# UBX_NORA_B1_SCHEM_0002_Power.net
KiCad netlist of a schematic drawn in Altium Designer
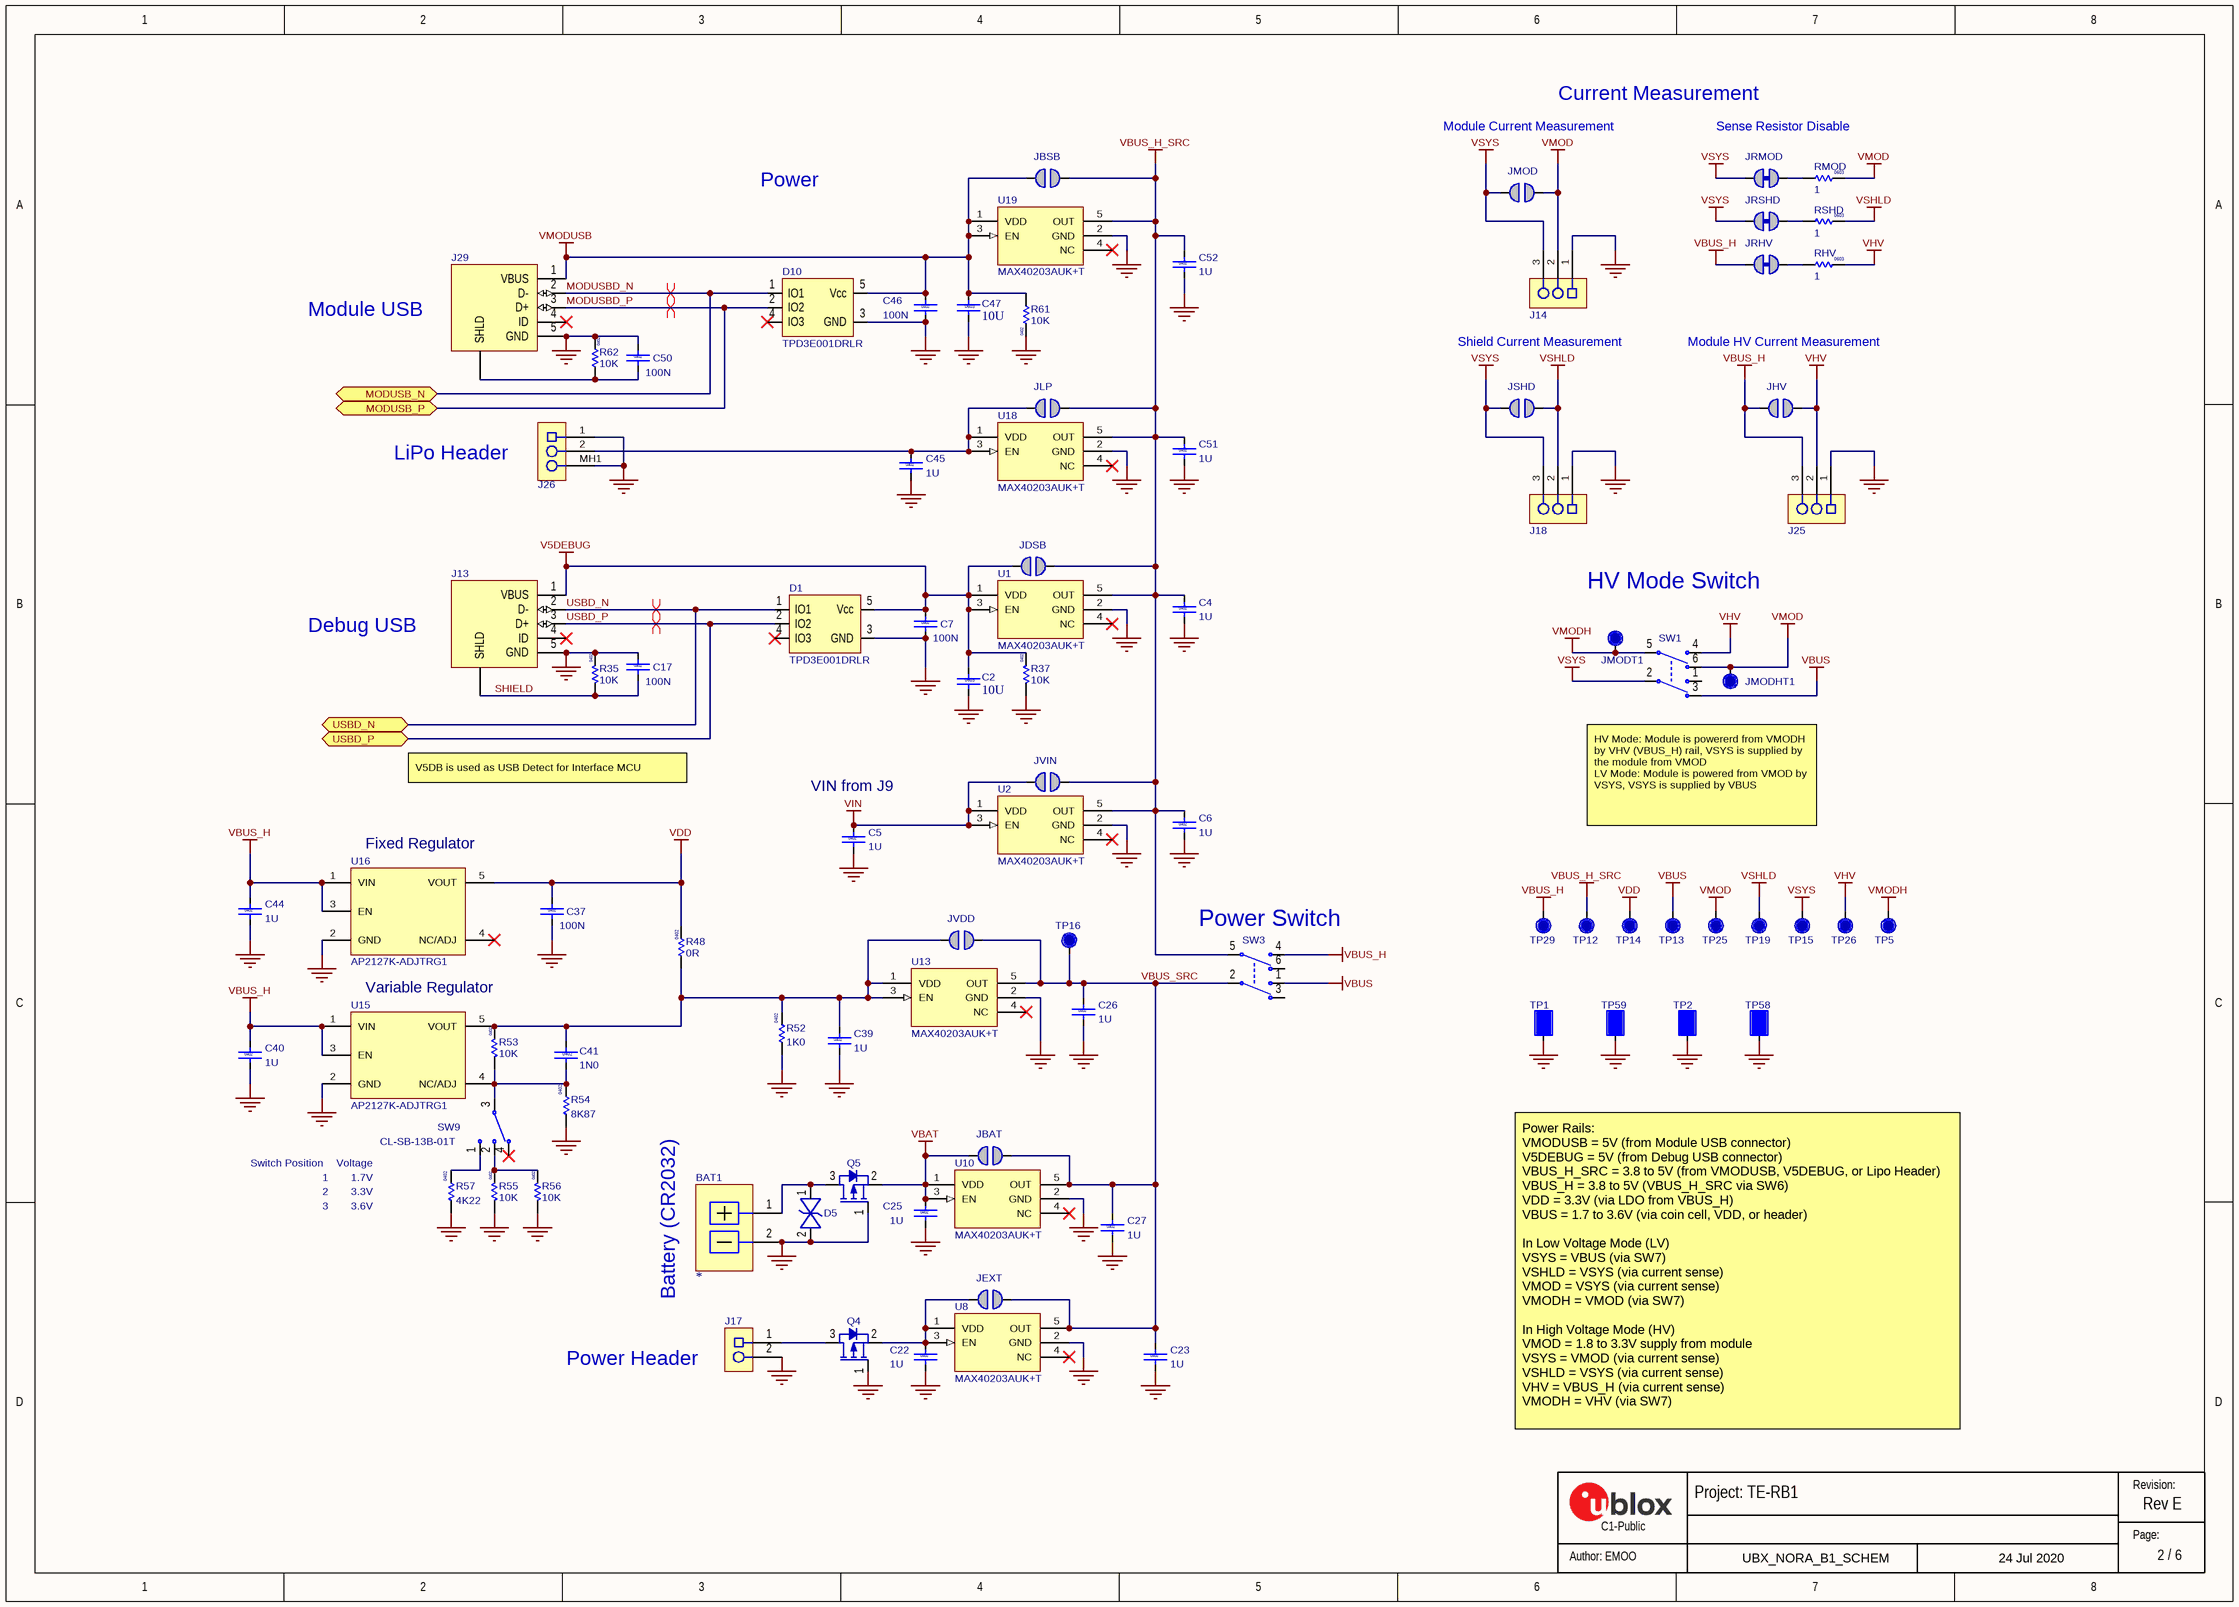
[diagram p0: UBX_NORA_B1_SCHEM_0002_Power.SchDoc]

(export (version "E")
  (design (tool "Eeschema 10.0.6"))
  (components
    (comp (ref "BAT1")
      (value "UBXH03-0000010")
      (footprint "Battery_S8211-46R_large")
      (description "BATTERY HOLDER COIN SMT CR2016 CR2020 CR2025 CR2032 HARWIN S8211-46R")
      (fields (field (name "MANUFACTURER P/N") "*") (field (name "EDITOR") "eric.moog"))
      (libsource (lib "UBX_Parts_DB_Lib") (part "Battery_2Pin"))
    )
    (comp (ref "C2")
      (value "10U")
      (footprint "CAP 0603 HD")
      (description "CAP CER X5R 0603 10U 20% 10V")
      (fields
        (field (name "SIZE") "0603")
        (field (name "PART NUMBER") "UBXH01-0000040")
        (field (name "TOLERANCE") "20%")
        (field (name "EDITOR") "pierpaolo.arban")
        (field (name "RELEASED BY") "matej.budin")
      )
      (libsource (lib "UBX_Parts_DB_Lib") (part "Cap Chip"))
    )
    (comp (ref "C4")
      (value "1U")
      (footprint "Cap 0402 HD")
      (description "CAP CER X5R 0402 1U 10% 10V")
      (fields
        (field (name "SIZE") "0402")
        (field (name "PART NUMBER") "UBXH01-0000248")
        (field (name "TOLERANCE") "10%")
        (field (name "EDITOR") "michael.hein")
        (field (name "RELEASED BY") "igor.shevchenko")
      )
      (libsource (lib "UBX_Parts_DB_Lib") (part "Cap Chip"))
    )
    (comp (ref "C5")
      (value "1U")
      (footprint "Cap 0402 HD")
      (description "CAP CER X5R 0402 1U 10% 10V")
      (fields
        (field (name "SIZE") "0402")
        (field (name "PART NUMBER") "UBXH01-0000248")
        (field (name "TOLERANCE") "10%")
        (field (name "EDITOR") "michael.hein")
        (field (name "RELEASED BY") "igor.shevchenko")
      )
      (libsource (lib "UBX_Parts_DB_Lib") (part "Cap Chip"))
    )
    (comp (ref "C6")
      (value "1U")
      (footprint "Cap 0402 HD")
      (description "CAP CER X5R 0402 1U 10% 10V")
      (fields
        (field (name "SIZE") "0402")
        (field (name "PART NUMBER") "UBXH01-0000248")
        (field (name "TOLERANCE") "10%")
        (field (name "EDITOR") "michael.hein")
        (field (name "RELEASED BY") "igor.shevchenko")
      )
      (libsource (lib "UBX_Parts_DB_Lib") (part "Cap Chip"))
    )
    (comp (ref "C7")
      (value "100N")
      (footprint "Cap 0402 HD")
      (description "CAP CER X5R 0402 100N 10% 10V")
      (fields
        (field (name "SIZE") "0402")
        (field (name "PART NUMBER") "UBXH01-2021002")
        (field (name "TOLERANCE") "10%")
        (field (name "EDITOR") "roland.rust")
        (field (name "RELEASED BY") "roland.rust")
      )
      (libsource (lib "UBX_Parts_DB_Lib") (part "Cap Chip"))
    )
    (comp (ref "C17")
      (value "100N")
      (footprint "Cap 0402 HD")
      (description "CAP CER X5R 0402 100N 10% 10V")
      (fields
        (field (name "SIZE") "0402")
        (field (name "PART NUMBER") "UBXH01-2021002")
        (field (name "TOLERANCE") "10%")
        (field (name "EDITOR") "roland.rust")
        (field (name "RELEASED BY") "roland.rust")
      )
      (libsource (lib "UBX_Parts_DB_Lib") (part "Cap Chip"))
    )
    (comp (ref "C22")
      (value "1U")
      (footprint "Cap 0402 HD")
      (description "CAP CER X5R 0402 1U 10% 10V")
      (fields
        (field (name "SIZE") "0402")
        (field (name "PART NUMBER") "UBXH01-0000248")
        (field (name "TOLERANCE") "10%")
        (field (name "EDITOR") "michael.hein")
        (field (name "RELEASED BY") "igor.shevchenko")
      )
      (libsource (lib "UBX_Parts_DB_Lib") (part "Cap Chip"))
    )
    (comp (ref "C23")
      (value "1U")
      (footprint "Cap 0402 HD")
      (description "CAP CER X5R 0402 1U 10% 10V")
      (fields
        (field (name "SIZE") "0402")
        (field (name "PART NUMBER") "UBXH01-0000248")
        (field (name "TOLERANCE") "10%")
        (field (name "EDITOR") "michael.hein")
        (field (name "RELEASED BY") "igor.shevchenko")
      )
      (libsource (lib "UBX_Parts_DB_Lib") (part "Cap Chip"))
    )
    (comp (ref "C25")
      (value "1U")
      (footprint "Cap 0402 HD")
      (description "CAP CER X5R 0402 1U 10% 10V")
      (fields
        (field (name "SIZE") "0402")
        (field (name "PART NUMBER") "UBXH01-0000248")
        (field (name "TOLERANCE") "10%")
        (field (name "EDITOR") "michael.hein")
        (field (name "RELEASED BY") "igor.shevchenko")
      )
      (libsource (lib "UBX_Parts_DB_Lib") (part "Cap Chip"))
    )
    (comp (ref "C26")
      (value "1U")
      (footprint "Cap 0402 HD")
      (description "CAP CER X5R 0402 1U 10% 10V")
      (fields
        (field (name "SIZE") "0402")
        (field (name "PART NUMBER") "UBXH01-0000248")
        (field (name "TOLERANCE") "10%")
        (field (name "EDITOR") "michael.hein")
        (field (name "RELEASED BY") "igor.shevchenko")
      )
      (libsource (lib "UBX_Parts_DB_Lib") (part "Cap Chip"))
    )
    (comp (ref "C27")
      (value "1U")
      (footprint "Cap 0402 HD")
      (description "CAP CER X5R 0402 1U 10% 10V")
      (fields
        (field (name "SIZE") "0402")
        (field (name "PART NUMBER") "UBXH01-0000248")
        (field (name "TOLERANCE") "10%")
        (field (name "EDITOR") "michael.hein")
        (field (name "RELEASED BY") "igor.shevchenko")
      )
      (libsource (lib "UBX_Parts_DB_Lib") (part "Cap Chip"))
    )
    (comp (ref "C37")
      (value "100N")
      (footprint "Cap 0402 HD")
      (description "CAP CER X5R 0402 100N 10% 10V")
      (fields
        (field (name "SIZE") "0402")
        (field (name "PART NUMBER") "UBXH01-2021002")
        (field (name "TOLERANCE") "10%")
        (field (name "EDITOR") "roland.rust")
        (field (name "RELEASED BY") "roland.rust")
      )
      (libsource (lib "UBX_Parts_DB_Lib") (part "Cap Chip"))
    )
    (comp (ref "C39")
      (value "1U")
      (footprint "Cap 0402 HD")
      (description "CAP CER X5R 0402 1U 10% 10V")
      (fields
        (field (name "SIZE") "0402")
        (field (name "PART NUMBER") "UBXH01-0000248")
        (field (name "TOLERANCE") "10%")
        (field (name "EDITOR") "michael.hein")
        (field (name "RELEASED BY") "igor.shevchenko")
      )
      (libsource (lib "UBX_Parts_DB_Lib") (part "Cap Chip"))
    )
    (comp (ref "C40")
      (value "1U")
      (footprint "Cap 0402 HD")
      (description "CAP CER X5R 0402 1U 10% 10V")
      (fields
        (field (name "SIZE") "0402")
        (field (name "PART NUMBER") "UBXH01-0000248")
        (field (name "TOLERANCE") "10%")
        (field (name "EDITOR") "michael.hein")
        (field (name "RELEASED BY") "igor.shevchenko")
      )
      (libsource (lib "UBX_Parts_DB_Lib") (part "Cap Chip"))
    )
    (comp (ref "C41")
      (value "1N0")
      (footprint "Cap 0402 HD")
      (description "CAP CER X7R 0402 1N0 10% 50V")
      (fields
        (field (name "SIZE") "0402")
        (field (name "PART NUMBER") "UBXH01-0000013")
        (field (name "TOLERANCE") "10%")
        (field (name "EDITOR") "massimo.vlacci")
        (field (name "RELEASED BY") "dario.antonaz")
      )
      (libsource (lib "UBX_Parts_DB_Lib") (part "Cap Chip"))
    )
    (comp (ref "C44")
      (value "1U")
      (footprint "Cap 0402 HD")
      (description "CAP CER X5R 0402 1U 10% 10V")
      (fields
        (field (name "SIZE") "0402")
        (field (name "PART NUMBER") "UBXH01-0000248")
        (field (name "TOLERANCE") "10%")
        (field (name "EDITOR") "michael.hein")
        (field (name "RELEASED BY") "igor.shevchenko")
      )
      (libsource (lib "UBX_Parts_DB_Lib") (part "Cap Chip"))
    )
    (comp (ref "C45")
      (value "1U")
      (footprint "Cap 0402 HD")
      (description "CAP CER X5R 0402 1U 10% 10V")
      (fields
        (field (name "SIZE") "0402")
        (field (name "PART NUMBER") "UBXH01-0000248")
        (field (name "TOLERANCE") "10%")
        (field (name "EDITOR") "michael.hein")
        (field (name "RELEASED BY") "igor.shevchenko")
      )
      (libsource (lib "UBX_Parts_DB_Lib") (part "Cap Chip"))
    )
    (comp (ref "C46")
      (value "100N")
      (footprint "Cap 0402 HD")
      (description "CAP CER X5R 0402 100N 10% 10V")
      (fields
        (field (name "SIZE") "0402")
        (field (name "PART NUMBER") "UBXH01-2021002")
        (field (name "TOLERANCE") "10%")
        (field (name "EDITOR") "roland.rust")
        (field (name "RELEASED BY") "roland.rust")
      )
      (libsource (lib "UBX_Parts_DB_Lib") (part "Cap Chip"))
    )
    (comp (ref "C47")
      (value "10U")
      (footprint "CAP 0603 HD")
      (description "CAP CER X5R 0603 10U 20% 10V")
      (fields
        (field (name "SIZE") "0603")
        (field (name "PART NUMBER") "UBXH01-0000040")
        (field (name "TOLERANCE") "20%")
        (field (name "EDITOR") "pierpaolo.arban")
        (field (name "RELEASED BY") "matej.budin")
      )
      (libsource (lib "UBX_Parts_DB_Lib") (part "Cap Chip"))
    )
    (comp (ref "C50")
      (value "100N")
      (footprint "Cap 0402 HD")
      (description "CAP CER X5R 0402 100N 10% 10V")
      (fields
        (field (name "SIZE") "0402")
        (field (name "PART NUMBER") "UBXH01-2021002")
        (field (name "TOLERANCE") "10%")
        (field (name "EDITOR") "roland.rust")
        (field (name "RELEASED BY") "roland.rust")
      )
      (libsource (lib "UBX_Parts_DB_Lib") (part "Cap Chip"))
    )
    (comp (ref "C51")
      (value "1U")
      (footprint "Cap 0402 HD")
      (description "CAP CER X5R 0402 1U 10% 10V")
      (fields
        (field (name "SIZE") "0402")
        (field (name "PART NUMBER") "UBXH01-0000248")
        (field (name "TOLERANCE") "10%")
        (field (name "EDITOR") "michael.hein")
        (field (name "RELEASED BY") "igor.shevchenko")
      )
      (libsource (lib "UBX_Parts_DB_Lib") (part "Cap Chip"))
    )
    (comp (ref "C52")
      (value "1U")
      (footprint "Cap 0402 HD")
      (description "CAP CER X5R 0402 1U 10% 10V")
      (fields
        (field (name "SIZE") "0402")
        (field (name "PART NUMBER") "UBXH01-0000248")
        (field (name "TOLERANCE") "10%")
        (field (name "EDITOR") "michael.hein")
        (field (name "RELEASED BY") "igor.shevchenko")
      )
      (libsource (lib "UBX_Parts_DB_Lib") (part "Cap Chip"))
    )
    (comp (ref "D1")
      (value "UBXH07-0000086")
      (footprint "SOT-553")
      (description "TVS DIODE 5.5VWM")
      (fields
        (field (name "MANUFACTURER P/N") "TPD3E001DRLR")
        (field (name "MANUFACTURER") "Texas Instruments")
        (field (name "EDITOR") "hozaifa.abdelgadir")
      )
      (libsource (lib "UBX_Parts_DB_Lib") (part "TPD3E001"))
    )
    (comp (ref "D5")
      (value "UBXH07-0000034")
      (footprint "SOD-923")
      (description "ESD PROTECTION DIODE ULTRA LOW LEAKAGE SOD923 ON SEMI 3V3")
      (fields
        (field (name "MANUFACTURER") "ON Semiconductor")
        (field (name "EDITOR") "pierpaolo.arban")
        (field (name "RELEASED BY") "dario.antonaz")
      )
      (libsource (lib "UBX_Parts_DB_Lib") (part "Diode_TVS"))
    )
    (comp (ref "D10")
      (value "UBXH07-0000086")
      (footprint "SOT-553")
      (description "TVS DIODE 5.5VWM")
      (fields
        (field (name "MANUFACTURER P/N") "TPD3E001DRLR")
        (field (name "MANUFACTURER") "Texas Instruments")
        (field (name "EDITOR") "hozaifa.abdelgadir")
      )
      (libsource (lib "UBX_Parts_DB_Lib") (part "TPD3E001"))
    )
    (comp (ref "J13")
      (value "UBXH04-0000804")
      (footprint "USB_MICRO_RA_W-2TABS")
      (description "CONN RECEPTACLE USB MICRO B 5-PIN SMD TH RA 5.5V 1.8A")
      (fields
        (field (name "MANUFACTURER") "Amphenol Commercial Products (Amphenol ICC)")
        (field (name "EDITOR") "eric.moog")
      )
      (libsource (lib "UBX_Parts_DB_Lib") (part "USB_W-Shield"))
    )
    (comp (ref "J14")
      (value "UBXH04-0000792")
      (footprint "HDR-0.1P-3Pin-1Row-SMT")
      (description "1-ROW SMD CONN 100MIL GRID 3 -PIN 100V 3A")
      (fields (field (name "MANUFACTURER") "HARWiN") (field (name "EDITOR") "eric.moog"))
      (libsource (lib "UBX_Parts_DB_Lib") (part "CON-3Pin_1Row"))
    )
    (comp (ref "J17")
      (value "UBXH04-0000026")
      (footprint "HDR-0.1P-2PIN-TH")
      (description "1-ROW TH-PCB SOCKETS 100MIL GRID 2-PIN 0.64MM SQUARE POLARIZE")
      (fields
        (field (name "MANUFACTURER") "HARWiN")
        (field (name "EDITOR") "roland.rust")
        (field (name "RELEASED BY") "alvaro.nussbaum")
      )
      (libsource (lib "UBX_Parts_DB_Lib") (part "CON-2Pin_1Row"))
    )
    (comp (ref "J18")
      (value "UBXH04-0000792")
      (footprint "HDR-0.1P-3Pin-1Row-SMT")
      (description "1-ROW SMD CONN 100MIL GRID 3 -PIN 100V 3A")
      (fields (field (name "MANUFACTURER") "HARWiN") (field (name "EDITOR") "eric.moog"))
      (libsource (lib "UBX_Parts_DB_Lib") (part "CON-3Pin_1Row"))
    )
    (comp (ref "J25")
      (value "UBXH04-0000792")
      (footprint "HDR-0.1P-3Pin-1Row-SMT")
      (description "1-ROW SMD CONN 100MIL GRID 3 -PIN 100V 3A")
      (fields (field (name "MANUFACTURER") "HARWiN") (field (name "EDITOR") "eric.moog"))
      (libsource (lib "UBX_Parts_DB_Lib") (part "CON-3Pin_1Row"))
    )
    (comp (ref "J26")
      (value "UBXH04-0000791")
      (footprint "B2B-PH-SM4-TB")
      (description "CONN 1-ROW SMT 2.0MM GRID 2-PIN VERT 100V 2A")
      (fields
        (field (name "VOLTAGE") "None")
        (field (name "MANUFACTURER") "JST")
        (field (name "EDITOR") "eric.moog")
      )
      (libsource (lib "UBX_Parts_DB_Lib") (part "CON-2Pin_1Row_W-MH"))
    )
    (comp (ref "J29")
      (value "UBXH04-0000804")
      (footprint "USB_MICRO_RA_W-2TABS")
      (description "CONN RECEPTACLE USB MICRO B 5-PIN SMD TH RA 5.5V 1.8A")
      (fields
        (field (name "MANUFACTURER") "Amphenol Commercial Products (Amphenol ICC)")
        (field (name "EDITOR") "eric.moog")
      )
      (libsource (lib "UBX_Parts_DB_Lib") (part "USB_W-Shield"))
    )
    (comp (ref "JBAT")
      (value "UBXH00-0000082")
      (footprint "Solderbridge-Open")
      (description "SOLDERBRIDGE-OPEN")
      (fields (field (name "EDITOR") "aneeb.sohail"))
      (libsource (lib "UBX_Parts_DB_Lib") (part "Solderbridge-Open"))
    )
    (comp (ref "JBSB")
      (value "UBXH00-0000082")
      (footprint "Solderbridge-Open")
      (description "SOLDERBRIDGE-OPEN")
      (fields (field (name "EDITOR") "aneeb.sohail"))
      (libsource (lib "UBX_Parts_DB_Lib") (part "Solderbridge-Open"))
    )
    (comp (ref "JDSB")
      (value "UBXH00-0000082")
      (footprint "Solderbridge-Open")
      (description "SOLDERBRIDGE-OPEN")
      (fields (field (name "EDITOR") "aneeb.sohail"))
      (libsource (lib "UBX_Parts_DB_Lib") (part "Solderbridge-Open"))
    )
    (comp (ref "JEXT")
      (value "UBXH00-0000082")
      (footprint "Solderbridge-Open")
      (description "SOLDERBRIDGE-OPEN")
      (fields (field (name "EDITOR") "aneeb.sohail"))
      (libsource (lib "UBX_Parts_DB_Lib") (part "Solderbridge-Open"))
    )
    (comp (ref "JHV")
      (value "UBXH00-0000082")
      (footprint "Solderbridge-Open")
      (description "SOLDERBRIDGE-OPEN")
      (fields (field (name "EDITOR") "aneeb.sohail"))
      (libsource (lib "UBX_Parts_DB_Lib") (part "Solderbridge-Open"))
    )
    (comp (ref "JLP")
      (value "UBXH00-0000082")
      (footprint "Solderbridge-Open")
      (description "SOLDERBRIDGE-OPEN")
      (fields (field (name "EDITOR") "aneeb.sohail"))
      (libsource (lib "UBX_Parts_DB_Lib") (part "Solderbridge-Open"))
    )
    (comp (ref "JMOD")
      (value "UBXH00-0000082")
      (footprint "Solderbridge-Open")
      (description "SOLDERBRIDGE-OPEN")
      (fields (field (name "EDITOR") "aneeb.sohail"))
      (libsource (lib "UBX_Parts_DB_Lib") (part "Solderbridge-Open"))
    )
    (comp (ref "JMODHT1")
      (value "TP")
      (footprint "TP10R")
      (description "TESTPOINT 1MM CIRCULAR")
      (fields (field (name "PART NUMBER") "UBXH00-0000096") (field (name "EDITOR") "eric.moog"))
      (libsource (lib "UBX_Parts_DB_Lib") (part "TP_R"))
    )
    (comp (ref "JMODT1")
      (value "TP")
      (footprint "TP10R")
      (description "TESTPOINT 1MM CIRCULAR")
      (fields (field (name "PART NUMBER") "UBXH00-0000096") (field (name "EDITOR") "eric.moog"))
      (libsource (lib "UBX_Parts_DB_Lib") (part "TP_R"))
    )
    (comp (ref "JRHV")
      (value "UBXH00-0000084")
      (footprint "Solderbridge-Short")
      (description "SOLDERBRIDGE-SHORT")
      (fields (field (name "EDITOR") "aneeb.sohail"))
      (libsource (lib "UBX_Parts_DB_Lib") (part "Solderbridge-Short"))
    )
    (comp (ref "JRMOD")
      (value "UBXH00-0000084")
      (footprint "Solderbridge-Short")
      (description "SOLDERBRIDGE-SHORT")
      (fields (field (name "EDITOR") "aneeb.sohail"))
      (libsource (lib "UBX_Parts_DB_Lib") (part "Solderbridge-Short"))
    )
    (comp (ref "JRSHD")
      (value "UBXH00-0000084")
      (footprint "Solderbridge-Short")
      (description "SOLDERBRIDGE-SHORT")
      (fields (field (name "EDITOR") "aneeb.sohail"))
      (libsource (lib "UBX_Parts_DB_Lib") (part "Solderbridge-Short"))
    )
    (comp (ref "JSHD")
      (value "UBXH00-0000082")
      (footprint "Solderbridge-Open")
      (description "SOLDERBRIDGE-OPEN")
      (fields (field (name "EDITOR") "aneeb.sohail"))
      (libsource (lib "UBX_Parts_DB_Lib") (part "Solderbridge-Open"))
    )
    (comp (ref "JVDD")
      (value "UBXH00-0000082")
      (footprint "Solderbridge-Open")
      (description "SOLDERBRIDGE-OPEN")
      (fields (field (name "EDITOR") "aneeb.sohail"))
      (libsource (lib "UBX_Parts_DB_Lib") (part "Solderbridge-Open"))
    )
    (comp (ref "JVIN")
      (value "UBXH00-0000082")
      (footprint "Solderbridge-Open")
      (description "SOLDERBRIDGE-OPEN")
      (fields (field (name "EDITOR") "aneeb.sohail"))
      (libsource (lib "UBX_Parts_DB_Lib") (part "Solderbridge-Open"))
    )
    (comp (ref "Q4")
      (value "UBXH20-0000087")
      (footprint "SOT-523")
      (description "P-CHANNEL MOSFET DIODES SOT-523 DMG1013T-7 20V 460mA")
      (fields (field (name "EDITOR") "eric.moog"))
      (libsource (lib "UBX_Parts_DB_Lib") (part "MOSFET-P"))
    )
    (comp (ref "Q5")
      (value "UBXH20-0000087")
      (footprint "SOT-523")
      (description "P-CHANNEL MOSFET DIODES SOT-523 DMG1013T-7 20V 460mA")
      (fields (field (name "EDITOR") "eric.moog"))
      (libsource (lib "UBX_Parts_DB_Lib") (part "MOSFET-P"))
    )
    (comp (ref "R35")
      (value "10K")
      (footprint "RES 0402 HD")
      (description "RES THICK FILM CHIP 0402 10K 1% 63mW")
      (fields
        (field (name "SIZE") "0402")
        (field (name "PART NUMBER") "UBXH18-0000065")
        (field (name "TOLERANCE") "1%")
        (field (name "EDITOR") "erian.bezhani")
        (field (name "RELEASED BY") "massimo.vlacci")
      )
      (libsource (lib "UBX_Parts_DB_Lib") (part "Res sm"))
    )
    (comp (ref "R37")
      (value "10K")
      (footprint "RES 0402 HD")
      (description "RES THICK FILM CHIP 0402 10K 1% 63mW")
      (fields
        (field (name "SIZE") "0402")
        (field (name "PART NUMBER") "UBXH18-0000065")
        (field (name "TOLERANCE") "1%")
        (field (name "EDITOR") "erian.bezhani")
        (field (name "RELEASED BY") "massimo.vlacci")
      )
      (libsource (lib "UBX_Parts_DB_Lib") (part "Res sm"))
    )
    (comp (ref "R48")
      (value "0R")
      (footprint "RES 0402 HD")
      (description "RES THICK FILM CHIP 0402 0R 0 100mW")
      (fields
        (field (name "SIZE") "0402")
        (field (name "PART NUMBER") "UBXH18-0003002")
        (field (name "TOLERANCE") "0")
        (field (name "EDITOR") "charlotte.biber")
        (field (name "RELEASED BY") "peter.mueller")
      )
      (libsource (lib "UBX_Parts_DB_Lib") (part "Res sm"))
    )
    (comp (ref "R52")
      (value "1K0")
      (footprint "RES 0402 HD")
      (description "RES THICK FILM CHIP 0402 1K0 5% 100mW")
      (fields
        (field (name "SIZE") "0402")
        (field (name "PART NUMBER") "UBXH18-0008049")
        (field (name "TOLERANCE") "5%")
        (field (name "EDITOR") "roland.rust")
        (field (name "RELEASED BY") "roland.rust")
      )
      (libsource (lib "UBX_Parts_DB_Lib") (part "Res sm"))
    )
    (comp (ref "R53")
      (value "10K")
      (footprint "RES 0402 HD")
      (description "RES THICK FILM CHIP 0402 10K 1% 63mW")
      (fields
        (field (name "SIZE") "0402")
        (field (name "PART NUMBER") "UBXH18-0000065")
        (field (name "TOLERANCE") "1%")
        (field (name "EDITOR") "erian.bezhani")
        (field (name "RELEASED BY") "massimo.vlacci")
      )
      (libsource (lib "UBX_Parts_DB_Lib") (part "Res sm"))
    )
    (comp (ref "R54")
      (value "8K87")
      (footprint "RES 0402 HD")
      (description "RES THICK FILM CHIP 0402 8K87 8K87 1% 63mW")
      (fields
        (field (name "SIZE") "0402")
        (field (name "PART NUMBER") "UBXH18-0000568")
        (field (name "TOLERANCE") "1%")
        (field (name "EDITOR") "eric.moog")
      )
      (libsource (lib "UBX_Parts_DB_Lib") (part "Res sm"))
    )
    (comp (ref "R55")
      (value "10K")
      (footprint "RES 0402 HD")
      (description "RES THICK FILM CHIP 0402 10K 1% 63mW")
      (fields
        (field (name "SIZE") "0402")
        (field (name "PART NUMBER") "UBXH18-0000065")
        (field (name "TOLERANCE") "1%")
        (field (name "EDITOR") "erian.bezhani")
        (field (name "RELEASED BY") "massimo.vlacci")
      )
      (libsource (lib "UBX_Parts_DB_Lib") (part "Res sm"))
    )
    (comp (ref "R56")
      (value "10K")
      (footprint "RES 0402 HD")
      (description "RES THICK FILM CHIP 0402 10K 1% 63mW")
      (fields
        (field (name "SIZE") "0402")
        (field (name "PART NUMBER") "UBXH18-0000065")
        (field (name "TOLERANCE") "1%")
        (field (name "EDITOR") "erian.bezhani")
        (field (name "RELEASED BY") "massimo.vlacci")
      )
      (libsource (lib "UBX_Parts_DB_Lib") (part "Res sm"))
    )
    (comp (ref "R57")
      (value "4K22")
      (footprint "RES 0402 HD")
      (description "RES THICK FILM CHIP 0402 4K22 4K22 1% 63mW")
      (fields
        (field (name "SIZE") "0402")
        (field (name "PART NUMBER") "UBXH18-0000569")
        (field (name "TOLERANCE") "1%")
        (field (name "EDITOR") "eric.moog")
      )
      (libsource (lib "UBX_Parts_DB_Lib") (part "Res sm"))
    )
    (comp (ref "R61")
      (value "10K")
      (footprint "RES 0402 HD")
      (description "RES THICK FILM CHIP 0402 10K 1% 63mW")
      (fields
        (field (name "SIZE") "0402")
        (field (name "PART NUMBER") "UBXH18-0000065")
        (field (name "TOLERANCE") "1%")
        (field (name "EDITOR") "erian.bezhani")
        (field (name "RELEASED BY") "massimo.vlacci")
      )
      (libsource (lib "UBX_Parts_DB_Lib") (part "Res sm"))
    )
    (comp (ref "R62")
      (value "10K")
      (footprint "RES 0402 HD")
      (description "RES THICK FILM CHIP 0402 10K 1% 63mW")
      (fields
        (field (name "SIZE") "0402")
        (field (name "PART NUMBER") "UBXH18-0000065")
        (field (name "TOLERANCE") "1%")
        (field (name "EDITOR") "erian.bezhani")
        (field (name "RELEASED BY") "massimo.vlacci")
      )
      (libsource (lib "UBX_Parts_DB_Lib") (part "Res sm"))
    )
    (comp (ref "RHV")
      (value "1")
      (footprint "RES_0603_1700Lx950Wx600H_600x1000Pad_800G_FLX")
      (description "RES THICK FILM CHIP 0603 200PPM/C 0.1W 1 1% 100mW")
      (fields
        (field (name "SIZE") "0603")
        (field (name "PART NUMBER") "UBXH18-0000555")
        (field (name "TOLERANCE") "1%")
        (field (name "EDITOR") "mikhail.sialitski")
        (field (name "RELEASED BY") "gianni.falleroni")
      )
      (libsource (lib "UBX_Parts_DB_Lib") (part "Res sm"))
    )
    (comp (ref "RMOD")
      (value "1")
      (footprint "RES_0603_1700Lx950Wx600H_600x1000Pad_800G_FLX")
      (description "RES THICK FILM CHIP 0603 200PPM/C 0.1W 1 1% 100mW")
      (fields
        (field (name "SIZE") "0603")
        (field (name "PART NUMBER") "UBXH18-0000555")
        (field (name "TOLERANCE") "1%")
        (field (name "EDITOR") "mikhail.sialitski")
        (field (name "RELEASED BY") "gianni.falleroni")
      )
      (libsource (lib "UBX_Parts_DB_Lib") (part "Res sm"))
    )
    (comp (ref "RSHD")
      (value "1")
      (footprint "RES_0603_1700Lx950Wx600H_600x1000Pad_800G_FLX")
      (description "RES THICK FILM CHIP 0603 200PPM/C 0.1W 1 1% 100mW")
      (fields
        (field (name "SIZE") "0603")
        (field (name "PART NUMBER") "UBXH18-0000555")
        (field (name "TOLERANCE") "1%")
        (field (name "EDITOR") "mikhail.sialitski")
        (field (name "RELEASED BY") "gianni.falleroni")
      )
      (libsource (lib "UBX_Parts_DB_Lib") (part "Res sm"))
    )
    (comp (ref "SW1")
      (value "UBXH19-0000050")
      (footprint "SW_Slide_DPDT_JS202011SCQN")
      (description "2 WAY ON-ON SUB-MINIATURE SLIDE SWITCH SMD JS SERIES")
      (fields
        (field (name "MANUFACTURER") "C&K Components")
        (field (name "EDITOR") "andre.pick")
        (field (name "RELEASED BY") "martin.pilik")
      )
      (libsource (lib "UBX_Parts_DB_Lib") (part "SW_DPDT_JS2020"))
    )
    (comp (ref "SW3")
      (value "UBXH19-0000050")
      (footprint "SW_Slide_DPDT_JS202011SCQN")
      (description "2 WAY ON-ON SUB-MINIATURE SLIDE SWITCH SMD JS SERIES")
      (fields
        (field (name "MANUFACTURER") "C&K Components")
        (field (name "EDITOR") "andre.pick")
        (field (name "RELEASED BY") "martin.pilik")
      )
      (libsource (lib "UBX_Parts_DB_Lib") (part "SW_DPDT_JS2020"))
    )
    (comp (ref "SW9")
      (value "UBXH19-0000039")
      (footprint "CL-SB-13B-01T")
      (description "3-WAY SLIDE SMD SWITCH SP3T")
      (fields
        (field (name "MANUFACTURER") "Nidec Copal Electronics")
        (field (name "VOLTAGE") "12V")
        (field (name "MANUFACTURER P/N") "CL-SB-13B-01T")
        (field (name "EDITOR") "evgenii.platonov")
      )
      (libsource (lib "UBX_Parts_DB_Lib") (part "CL-SB-13B-01T"))
    )
    (comp (ref "TP1")
      (value "UBXH00-0000097")
      (footprint "TP4.5x3Sq")
      (description "TESTPOINT 3MMX4.5MM RECTANGULAR NO SILKSCREEN")
      (fields (field (name "EDITOR") "eric.moog"))
      (libsource (lib "UBX_Parts_DB_Lib") (part "TP_Sq"))
    )
    (comp (ref "TP2")
      (value "UBXH00-0000097")
      (footprint "TP4.5x3Sq")
      (description "TESTPOINT 3MMX4.5MM RECTANGULAR NO SILKSCREEN")
      (fields (field (name "EDITOR") "eric.moog"))
      (libsource (lib "UBX_Parts_DB_Lib") (part "TP_Sq"))
    )
    (comp (ref "TP5")
      (value "TP")
      (footprint "TP12R")
      (description "TESTPOINT 1.2MM CIRCULAR W/ SILKSCREEN")
      (fields (field (name "PART NUMBER") "UBXH00-0000102") (field (name "EDITOR") "eric.moog"))
      (libsource (lib "UBX_Parts_DB_Lib") (part "TP_R"))
    )
    (comp (ref "TP12")
      (value "TP")
      (footprint "TP12R")
      (description "TESTPOINT 1.2MM CIRCULAR W/ SILKSCREEN")
      (fields (field (name "PART NUMBER") "UBXH00-0000102") (field (name "EDITOR") "eric.moog"))
      (libsource (lib "UBX_Parts_DB_Lib") (part "TP_R"))
    )
    (comp (ref "TP13")
      (value "TP")
      (footprint "TP12R")
      (description "TESTPOINT 1.2MM CIRCULAR W/ SILKSCREEN")
      (fields (field (name "PART NUMBER") "UBXH00-0000102") (field (name "EDITOR") "eric.moog"))
      (libsource (lib "UBX_Parts_DB_Lib") (part "TP_R"))
    )
    (comp (ref "TP14")
      (value "TP")
      (footprint "TP12R")
      (description "TESTPOINT 1.2MM CIRCULAR W/ SILKSCREEN")
      (fields (field (name "PART NUMBER") "UBXH00-0000102") (field (name "EDITOR") "eric.moog"))
      (libsource (lib "UBX_Parts_DB_Lib") (part "TP_R"))
    )
    (comp (ref "TP15")
      (value "TP")
      (footprint "TP12R")
      (description "TESTPOINT 1.2MM CIRCULAR")
      (fields (field (name "PART NUMBER") "UBXH00-0000102") (field (name "EDITOR") "eric.moog"))
      (libsource (lib "UBX_Parts_DB_Lib") (part "TP_R"))
    )
    (comp (ref "TP16")
      (value "TP")
      (footprint "TP10R")
      (description "TESTPOINT 1MM CIRCULAR")
      (fields (field (name "PART NUMBER") "UBXH00-0000096") (field (name "EDITOR") "eric.moog"))
      (libsource (lib "UBX_Parts_DB_Lib") (part "TP_R"))
    )
    (comp (ref "TP19")
      (value "TP")
      (footprint "TP12R")
      (description "TESTPOINT 1.2MM CIRCULAR W/ SILKSCREEN")
      (fields (field (name "PART NUMBER") "UBXH00-0000102") (field (name "EDITOR") "eric.moog"))
      (libsource (lib "UBX_Parts_DB_Lib") (part "TP_R"))
    )
    (comp (ref "TP25")
      (value "TP")
      (footprint "TP12R")
      (description "TESTPOINT 1.2MM CIRCULAR W/ SILKSCREEN")
      (fields (field (name "PART NUMBER") "UBXH00-0000102") (field (name "EDITOR") "eric.moog"))
      (libsource (lib "UBX_Parts_DB_Lib") (part "TP_R"))
    )
    (comp (ref "TP26")
      (value "TP")
      (footprint "TP12R")
      (description "TESTPOINT 1.2MM CIRCULAR W/ SILKSCREEN")
      (fields (field (name "PART NUMBER") "UBXH00-0000102") (field (name "EDITOR") "eric.moog"))
      (libsource (lib "UBX_Parts_DB_Lib") (part "TP_R"))
    )
    (comp (ref "TP29")
      (value "TP")
      (footprint "TP12R")
      (description "TESTPOINT 1.2MM CIRCULAR W/ SILKSCREEN")
      (fields (field (name "PART NUMBER") "UBXH00-0000102") (field (name "EDITOR") "eric.moog"))
      (libsource (lib "UBX_Parts_DB_Lib") (part "TP_R"))
    )
    (comp (ref "TP58")
      (value "UBXH00-0000097")
      (footprint "TP4.5x3Sq")
      (description "TESTPOINT 3MMX4.5MM RECTANGULAR NO SILKSCREEN")
      (fields (field (name "EDITOR") "eric.moog"))
      (libsource (lib "UBX_Parts_DB_Lib") (part "TP_Sq"))
    )
    (comp (ref "TP59")
      (value "UBXH00-0000097")
      (footprint "TP4.5x3Sq")
      (description "TESTPOINT 3MMX4.5MM RECTANGULAR NO SILKSCREEN")
      (fields (field (name "EDITOR") "eric.moog"))
      (libsource (lib "UBX_Parts_DB_Lib") (part "TP_Sq"))
    )
    (comp (ref "U1")
      (value "UBXH12-0000539")
      (footprint "SOT-23-5_2")
      (description "IDEAL DIODE OR CONTROLLER SOURCE SELECTOR SWITCH P-CHANNEL 1:1 SOT-23-5 5.5V 1A")
      (fields
        (field (name "VOLTAGE") "5.5V")
        (field (name "MANUFACTURER PART NUMBER 1") "MAX40203AUK+T")
        (field (name "MANUFACTURER") "Maxim")
        (field (name "EDITOR") "eric.moog")
      )
      (libsource (lib "UBX_Parts_DB_Lib") (part "MAX40203AUK"))
    )
    (comp (ref "U2")
      (value "UBXH12-0000539")
      (footprint "SOT-23-5_2")
      (description "IDEAL DIODE OR CONTROLLER SOURCE SELECTOR SWITCH P-CHANNEL 1:1 SOT-23-5 5.5V 1A")
      (fields
        (field (name "VOLTAGE") "5.5V")
        (field (name "MANUFACTURER PART NUMBER 1") "MAX40203AUK+T")
        (field (name "MANUFACTURER") "Maxim")
        (field (name "EDITOR") "eric.moog")
      )
      (libsource (lib "UBX_Parts_DB_Lib") (part "MAX40203AUK"))
    )
    (comp (ref "U8")
      (value "UBXH12-0000539")
      (footprint "SOT-23-5_2")
      (description "IDEAL DIODE OR CONTROLLER SOURCE SELECTOR SWITCH P-CHANNEL 1:1 SOT-23-5 5.5V 1A")
      (fields
        (field (name "VOLTAGE") "5.5V")
        (field (name "MANUFACTURER PART NUMBER 1") "MAX40203AUK+T")
        (field (name "MANUFACTURER") "Maxim")
        (field (name "EDITOR") "eric.moog")
      )
      (libsource (lib "UBX_Parts_DB_Lib") (part "MAX40203AUK"))
    )
    (comp (ref "U10")
      (value "UBXH12-0000539")
      (footprint "SOT-23-5_2")
      (description "IDEAL DIODE OR CONTROLLER SOURCE SELECTOR SWITCH P-CHANNEL 1:1 SOT-23-5 5.5V 1A")
      (fields
        (field (name "VOLTAGE") "5.5V")
        (field (name "MANUFACTURER PART NUMBER 1") "MAX40203AUK+T")
        (field (name "MANUFACTURER") "Maxim")
        (field (name "EDITOR") "eric.moog")
      )
      (libsource (lib "UBX_Parts_DB_Lib") (part "MAX40203AUK"))
    )
    (comp (ref "U13")
      (value "UBXH12-0000539")
      (footprint "SOT-23-5_2")
      (description "IDEAL DIODE OR CONTROLLER SOURCE SELECTOR SWITCH P-CHANNEL 1:1 SOT-23-5 5.5V 1A")
      (fields
        (field (name "VOLTAGE") "5.5V")
        (field (name "MANUFACTURER PART NUMBER 1") "MAX40203AUK+T")
        (field (name "MANUFACTURER") "Maxim")
        (field (name "EDITOR") "eric.moog")
      )
      (libsource (lib "UBX_Parts_DB_Lib") (part "MAX40203AUK"))
    )
    (comp (ref "U15")
      (value "UBXH12-0000547")
      (footprint "SOT-23-5_3D_Body_Fix")
      (description "LDO REGULATOR ADJ 3.3V 300MA AP2127 SOT-23-5 6V 300mA")
      (fields
        (field (name "VOLTAGE") "6V")
        (field (name "MANUFACTURER PART NUMBER 1") "AP2127K-ADJTRG1")
        (field (name "MANUFACTURER") "Diodes Incorporated")
        (field (name "EDITOR") "eric.moog")
      )
      (libsource (lib "UBX_Parts_DB_Lib") (part "AP2127K-ADJ"))
    )
    (comp (ref "U16")
      (value "UBXH12-0000546")
      (footprint "SOT-23-5_3D_Body_Fix")
      (description "LDO REGULATOR FIX 3.3V 300MA AP2127 SOT-23-5 6V 300mA")
      (fields
        (field (name "VOLTAGE") "6V")
        (field (name "MANUFACTURER PART NUMBER 1") "AP2127K-ADJTRG1")
        (field (name "MANUFACTURER") "Diodes Incorporated")
        (field (name "EDITOR") "eric.moog")
      )
      (libsource (lib "UBX_Parts_DB_Lib") (part "AP2127K-ADJ"))
    )
    (comp (ref "U18")
      (value "UBXH12-0000539")
      (footprint "SOT-23-5_2")
      (description "IDEAL DIODE OR CONTROLLER SOURCE SELECTOR SWITCH P-CHANNEL 1:1 SOT-23-5 5.5V 1A")
      (fields
        (field (name "VOLTAGE") "5.5V")
        (field (name "MANUFACTURER PART NUMBER 1") "MAX40203AUK+T")
        (field (name "MANUFACTURER") "Maxim")
        (field (name "EDITOR") "eric.moog")
      )
      (libsource (lib "UBX_Parts_DB_Lib") (part "MAX40203AUK"))
    )
    (comp (ref "U19")
      (value "UBXH12-0000539")
      (footprint "SOT-23-5_2")
      (description "IDEAL DIODE OR CONTROLLER SOURCE SELECTOR SWITCH P-CHANNEL 1:1 SOT-23-5 5.5V 1A")
      (fields
        (field (name "VOLTAGE") "5.5V")
        (field (name "MANUFACTURER PART NUMBER 1") "MAX40203AUK+T")
        (field (name "MANUFACTURER") "Maxim")
        (field (name "EDITOR") "eric.moog")
      )
      (libsource (lib "UBX_Parts_DB_Lib") (part "MAX40203AUK"))
    )
  )
  (nets
    (net (code "1") (name "/MODUSBD_N") (class "Default")
      (node (ref "D10") (pin "1") (pinfunction "IO1_1") (pintype "passive"))
      (node (ref "J29") (pin "2") (pinfunction "D-_2") (pintype "bidirectional"))
    )
    (net (code "2") (name "/MODUSBD_P") (class "Default")
      (node (ref "D10") (pin "2") (pinfunction "IO2_2") (pintype "passive"))
      (node (ref "J29") (pin "3") (pinfunction "D+_3") (pintype "bidirectional"))
    )
    (net (code "3") (name "/SHIELD") (class "Default")
      (node (ref "C17") (pin "2") (pinfunction "2_2") (pintype "passive"))
      (node (ref "J13") (pin "6") (pinfunction "SHLD_6") (pintype "passive"))
      (node (ref "R35") (pin "1") (pinfunction "1_1") (pintype "passive"))
    )
    (net (code "4") (name "/USBD_N") (class "Default")
      (node (ref "D1") (pin "1") (pinfunction "IO1_1") (pintype "passive"))
      (node (ref "J13") (pin "2") (pinfunction "D-_2") (pintype "bidirectional"))
    )
    (net (code "5") (name "/USBD_P") (class "Default")
      (node (ref "D1") (pin "2") (pinfunction "IO2_2") (pintype "passive"))
      (node (ref "J13") (pin "3") (pinfunction "D+_3") (pintype "bidirectional"))
    )
    (net (code "6") (name "/VBUS_SRC") (class "Default")
      (node (ref "C23") (pin "1") (pinfunction "1_1") (pintype "passive"))
      (node (ref "C26") (pin "1") (pinfunction "1_1") (pintype "passive"))
      (node (ref "C27") (pin "1") (pinfunction "1_1") (pintype "passive"))
      (node (ref "JBAT") (pin "1") (pinfunction "1_1") (pintype "passive"))
      (node (ref "JEXT") (pin "1") (pinfunction "1_1") (pintype "passive"))
      (node (ref "JVDD") (pin "1") (pinfunction "1_1") (pintype "passive"))
      (node (ref "SW3") (pin "2") (pinfunction "COM-1_2") (pintype "passive"))
      (node (ref "TP16") (pin "1") (pintype "passive"))
      (node (ref "U10") (pin "5") (pinfunction "OUT_5") (pintype "power_in"))
      (node (ref "U13") (pin "5") (pinfunction "OUT_5") (pintype "power_in"))
      (node (ref "U8") (pin "5") (pinfunction "OUT_5") (pintype "power_in"))
    )
    (net (code "7") (name "GND") (class "Default")
      (node (ref "BAT1") (pin "2") (pinfunction "2_2") (pintype "power_in"))
      (node (ref "C17") (pin "1") (pinfunction "1_1") (pintype "passive"))
      (node (ref "C2") (pin "2") (pinfunction "2_2") (pintype "passive"))
      (node (ref "C22") (pin "2") (pinfunction "2_2") (pintype "passive"))
      (node (ref "C23") (pin "2") (pinfunction "2_2") (pintype "passive"))
      (node (ref "C25") (pin "2") (pinfunction "2_2") (pintype "passive"))
      (node (ref "C26") (pin "2") (pinfunction "2_2") (pintype "passive"))
      (node (ref "C27") (pin "2") (pinfunction "2_2") (pintype "passive"))
      (node (ref "C37") (pin "2") (pinfunction "2_2") (pintype "passive"))
      (node (ref "C39") (pin "2") (pinfunction "2_2") (pintype "passive"))
      (node (ref "C4") (pin "2") (pinfunction "2_2") (pintype "passive"))
      (node (ref "C40") (pin "2") (pinfunction "2_2") (pintype "passive"))
      (node (ref "C44") (pin "2") (pinfunction "2_2") (pintype "passive"))
      (node (ref "C45") (pin "2") (pinfunction "2_2") (pintype "passive"))
      (node (ref "C46") (pin "2") (pinfunction "2_2") (pintype "passive"))
      (node (ref "C47") (pin "2") (pinfunction "2_2") (pintype "passive"))
      (node (ref "C5") (pin "2") (pinfunction "2_2") (pintype "passive"))
      (node (ref "C50") (pin "1") (pinfunction "1_1") (pintype "passive"))
      (node (ref "C51") (pin "2") (pinfunction "2_2") (pintype "passive"))
      (node (ref "C52") (pin "2") (pinfunction "2_2") (pintype "passive"))
      (node (ref "C6") (pin "2") (pinfunction "2_2") (pintype "passive"))
      (node (ref "C7") (pin "2") (pinfunction "2_2") (pintype "passive"))
      (node (ref "D1") (pin "3") (pinfunction "GND_3") (pintype "power_in"))
      (node (ref "D10") (pin "3") (pinfunction "GND_3") (pintype "power_in"))
      (node (ref "D5") (pin "2") (pintype "passive"))
      (node (ref "J13") (pin "5") (pinfunction "GND_5") (pintype "power_in"))
      (node (ref "J14") (pin "1") (pinfunction "1_1") (pintype "passive"))
      (node (ref "J17") (pin "2") (pinfunction "2_2") (pintype "passive"))
      (node (ref "J18") (pin "1") (pinfunction "1_1") (pintype "passive"))
      (node (ref "J25") (pin "1") (pinfunction "1_1") (pintype "passive"))
      (node (ref "J26") (pin "1") (pinfunction "1_1") (pintype "passive"))
      (node (ref "J26") (pin "MH1") (pinfunction "MH1_MH1") (pintype "passive"))
      (node (ref "J29") (pin "5") (pinfunction "GND_5") (pintype "power_in"))
      (node (ref "Q4") (pin "1") (pinfunction "G_1") (pintype "passive"))
      (node (ref "Q5") (pin "1") (pinfunction "G_1") (pintype "passive"))
      (node (ref "R35") (pin "2") (pinfunction "2_2") (pintype "passive"))
      (node (ref "R37") (pin "1") (pinfunction "1_1") (pintype "passive"))
      (node (ref "R52") (pin "1") (pinfunction "1_1") (pintype "passive"))
      (node (ref "R54") (pin "1") (pinfunction "1_1") (pintype "passive"))
      (node (ref "R55") (pin "1") (pinfunction "1_1") (pintype "passive"))
      (node (ref "R56") (pin "1") (pinfunction "1_1") (pintype "passive"))
      (node (ref "R57") (pin "1") (pinfunction "1_1") (pintype "passive"))
      (node (ref "R61") (pin "2") (pinfunction "2_2") (pintype "passive"))
      (node (ref "R62") (pin "2") (pinfunction "2_2") (pintype "passive"))
      (node (ref "TP1") (pin "1") (pintype "passive"))
      (node (ref "TP2") (pin "1") (pintype "passive"))
      (node (ref "TP58") (pin "1") (pintype "passive"))
      (node (ref "TP59") (pin "1") (pintype "passive"))
      (node (ref "U1") (pin "2") (pinfunction "GND_2") (pintype "power_in"))
      (node (ref "U10") (pin "2") (pinfunction "GND_2") (pintype "power_in"))
      (node (ref "U13") (pin "2") (pinfunction "GND_2") (pintype "power_in"))
      (node (ref "U15") (pin "2") (pinfunction "GND_2") (pintype "power_in"))
      (node (ref "U16") (pin "2") (pinfunction "GND_2") (pintype "power_in"))
      (node (ref "U18") (pin "2") (pinfunction "GND_2") (pintype "power_in"))
      (node (ref "U19") (pin "2") (pinfunction "GND_2") (pintype "power_in"))
      (node (ref "U2") (pin "2") (pinfunction "GND_2") (pintype "power_in"))
      (node (ref "U8") (pin "2") (pinfunction "GND_2") (pintype "power_in"))
    )
    (net (code "8") (name "Net-(J29-SHLD)") (class "Default")
      (node (ref "C50") (pin "2") (pinfunction "2_2") (pintype "passive"))
      (node (ref "J29") (pin "6") (pinfunction "SHLD_6") (pintype "passive"))
      (node (ref "R62") (pin "1") (pinfunction "1_1") (pintype "passive"))
    )
    (net (code "9") (name "Net-(JRHV-Pad1)") (class "Default")
      (node (ref "JRHV") (pin "1") (pinfunction "1_1") (pintype "passive"))
      (node (ref "RHV") (pin "1") (pinfunction "1_1") (pintype "passive"))
    )
    (net (code "10") (name "Net-(JRMOD-Pad1)") (class "Default")
      (node (ref "JRMOD") (pin "1") (pinfunction "1_1") (pintype "passive"))
      (node (ref "RMOD") (pin "1") (pinfunction "1_1") (pintype "passive"))
    )
    (net (code "11") (name "Net-(JRSHD-Pad1)") (class "Default")
      (node (ref "JRSHD") (pin "1") (pinfunction "1_1") (pintype "passive"))
      (node (ref "RSHD") (pin "1") (pinfunction "1_1") (pintype "passive"))
    )
    (net (code "12") (name "Net-(Q4-D)") (class "Default")
      (node (ref "J17") (pin "1") (pinfunction "1_1") (pintype "passive"))
      (node (ref "Q4") (pin "3") (pinfunction "D_3") (pintype "passive"))
    )
    (net (code "13") (name "Net-(Q4-S)") (class "Default")
      (node (ref "C22") (pin "1") (pinfunction "1_1") (pintype "passive"))
      (node (ref "JEXT") (pin "2") (pinfunction "2_2") (pintype "passive"))
      (node (ref "Q4") (pin "2") (pinfunction "S_2") (pintype "passive"))
      (node (ref "U8") (pin "1") (pinfunction "VDD_1") (pintype "power_in"))
      (node (ref "U8") (pin "3") (pinfunction "EN_3") (pintype "input"))
    )
    (net (code "14") (name "Net-(Q5-D)") (class "Default")
      (node (ref "BAT1") (pin "1") (pinfunction "1_1") (pintype "power_in"))
      (node (ref "D5") (pin "1") (pintype "passive"))
      (node (ref "Q5") (pin "3") (pinfunction "D_3") (pintype "passive"))
    )
    (net (code "15") (name "Net-(SW9-COM)") (class "Default")
      (node (ref "C41") (pin "2") (pinfunction "2_2") (pintype "passive"))
      (node (ref "R53") (pin "1") (pinfunction "1_1") (pintype "passive"))
      (node (ref "R54") (pin "2") (pinfunction "2_2") (pintype "passive"))
      (node (ref "SW9") (pin "3") (pinfunction "COM_3") (pintype "passive"))
      (node (ref "U15") (pin "4") (pinfunction "NC/ADJ_4") (pintype "passive"))
    )
    (net (code "16") (name "Net-(SW9-N.O-1)") (class "Default")
      (node (ref "R57") (pin "2") (pinfunction "2_2") (pintype "passive"))
      (node (ref "SW9") (pin "1") (pinfunction "N.O-1_1") (pintype "passive"))
    )
    (net (code "17") (name "Net-(SW9-N.O-2)") (class "Default")
      (node (ref "R55") (pin "2") (pinfunction "2_2") (pintype "passive"))
      (node (ref "R56") (pin "2") (pinfunction "2_2") (pintype "passive"))
      (node (ref "SW9") (pin "2") (pinfunction "N.O-2_2") (pintype "passive"))
    )
    (net (code "18") (name "Net-(U13-EN)") (class "Default")
      (node (ref "C39") (pin "1") (pinfunction "1_1") (pintype "passive"))
      (node (ref "C41") (pin "1") (pinfunction "1_1") (pintype "passive"))
      (node (ref "JVDD") (pin "2") (pinfunction "2_2") (pintype "passive"))
      (node (ref "R48") (pin "1") (pinfunction "1_1") (pintype "passive"))
      (node (ref "R52") (pin "2") (pinfunction "2_2") (pintype "passive"))
      (node (ref "R53") (pin "2") (pinfunction "2_2") (pintype "passive"))
      (node (ref "U13") (pin "1") (pinfunction "VDD_1") (pintype "power_in"))
      (node (ref "U13") (pin "3") (pinfunction "EN_3") (pintype "input"))
      (node (ref "U15") (pin "5") (pinfunction "VOUT_5") (pintype "power_in"))
    )
    (net (code "19") (name "Net-(U18-EN)") (class "Default")
      (node (ref "C45") (pin "1") (pinfunction "1_1") (pintype "passive"))
      (node (ref "J26") (pin "2") (pinfunction "2_2") (pintype "passive"))
      (node (ref "JLP") (pin "2") (pinfunction "2_2") (pintype "passive"))
      (node (ref "U18") (pin "1") (pinfunction "VDD_1") (pintype "power_in"))
      (node (ref "U18") (pin "3") (pinfunction "EN_3") (pintype "input"))
    )
    (net (code "20") (name "V5DEBUG") (class "Default")
      (node (ref "C2") (pin "1") (pinfunction "1_1") (pintype "passive"))
      (node (ref "C7") (pin "1") (pinfunction "1_1") (pintype "passive"))
      (node (ref "D1") (pin "5") (pinfunction "Vcc_5") (pintype "power_in"))
      (node (ref "J13") (pin "1") (pinfunction "VBUS_1") (pintype "power_in"))
      (node (ref "JDSB") (pin "2") (pinfunction "2_2") (pintype "passive"))
      (node (ref "R37") (pin "2") (pinfunction "2_2") (pintype "passive"))
      (node (ref "U1") (pin "1") (pinfunction "VDD_1") (pintype "power_in"))
      (node (ref "U1") (pin "3") (pinfunction "EN_3") (pintype "input"))
    )
    (net (code "21") (name "VBAT") (class "Default")
      (node (ref "C25") (pin "1") (pinfunction "1_1") (pintype "passive"))
      (node (ref "JBAT") (pin "2") (pinfunction "2_2") (pintype "passive"))
      (node (ref "Q5") (pin "2") (pinfunction "S_2") (pintype "passive"))
      (node (ref "U10") (pin "1") (pinfunction "VDD_1") (pintype "power_in"))
      (node (ref "U10") (pin "3") (pinfunction "EN_3") (pintype "input"))
    )
    (net (code "22") (name "VBUS") (class "Default")
      (node (ref "SW1") (pin "3") (pinfunction "N.C-1_3") (pintype "passive"))
      (node (ref "SW3") (pin "1") (pinfunction "N.O-1_1") (pintype "passive"))
      (node (ref "TP13") (pin "1") (pintype "passive"))
    )
    (net (code "23") (name "VBUS_H") (class "Default")
      (node (ref "C40") (pin "1") (pinfunction "1_1") (pintype "passive"))
      (node (ref "C44") (pin "1") (pinfunction "1_1") (pintype "passive"))
      (node (ref "J25") (pin "3") (pinfunction "3_3") (pintype "passive"))
      (node (ref "JHV") (pin "2") (pinfunction "2_2") (pintype "passive"))
      (node (ref "JRHV") (pin "2") (pinfunction "2_2") (pintype "passive"))
      (node (ref "SW3") (pin "4") (pinfunction "N.O-2_4") (pintype "passive"))
      (node (ref "TP29") (pin "1") (pintype "passive"))
      (node (ref "U15") (pin "1") (pinfunction "VIN_1") (pintype "power_in"))
      (node (ref "U15") (pin "3") (pinfunction "EN_3") (pintype "passive"))
      (node (ref "U16") (pin "1") (pinfunction "VIN_1") (pintype "power_in"))
      (node (ref "U16") (pin "3") (pinfunction "EN_3") (pintype "passive"))
    )
    (net (code "24") (name "VBUS_H_SRC") (class "Default")
      (node (ref "C4") (pin "1") (pinfunction "1_1") (pintype "passive"))
      (node (ref "C51") (pin "1") (pinfunction "1_1") (pintype "passive"))
      (node (ref "C52") (pin "1") (pinfunction "1_1") (pintype "passive"))
      (node (ref "C6") (pin "1") (pinfunction "1_1") (pintype "passive"))
      (node (ref "JBSB") (pin "1") (pinfunction "1_1") (pintype "passive"))
      (node (ref "JDSB") (pin "1") (pinfunction "1_1") (pintype "passive"))
      (node (ref "JLP") (pin "1") (pinfunction "1_1") (pintype "passive"))
      (node (ref "JVIN") (pin "1") (pinfunction "1_1") (pintype "passive"))
      (node (ref "SW3") (pin "5") (pinfunction "COM-2_5") (pintype "passive"))
      (node (ref "TP12") (pin "1") (pintype "passive"))
      (node (ref "U1") (pin "5") (pinfunction "OUT_5") (pintype "power_in"))
      (node (ref "U18") (pin "5") (pinfunction "OUT_5") (pintype "power_in"))
      (node (ref "U19") (pin "5") (pinfunction "OUT_5") (pintype "power_in"))
      (node (ref "U2") (pin "5") (pinfunction "OUT_5") (pintype "power_in"))
    )
    (net (code "25") (name "VDD") (class "Default")
      (node (ref "C37") (pin "1") (pinfunction "1_1") (pintype "passive"))
      (node (ref "R48") (pin "2") (pinfunction "2_2") (pintype "passive"))
      (node (ref "TP14") (pin "1") (pintype "passive"))
      (node (ref "U16") (pin "5") (pinfunction "VOUT_5") (pintype "power_in"))
    )
    (net (code "26") (name "VHV") (class "Default")
      (node (ref "J25") (pin "2") (pinfunction "2_2") (pintype "passive"))
      (node (ref "JHV") (pin "1") (pinfunction "1_1") (pintype "passive"))
      (node (ref "RHV") (pin "2") (pinfunction "2_2") (pintype "passive"))
      (node (ref "SW1") (pin "4") (pinfunction "N.O-2_4") (pintype "passive"))
      (node (ref "TP26") (pin "1") (pintype "passive"))
    )
    (net (code "27") (name "VIN") (class "Default")
      (node (ref "C5") (pin "1") (pinfunction "1_1") (pintype "passive"))
      (node (ref "JVIN") (pin "2") (pinfunction "2_2") (pintype "passive"))
      (node (ref "U2") (pin "1") (pinfunction "VDD_1") (pintype "power_in"))
      (node (ref "U2") (pin "3") (pinfunction "EN_3") (pintype "input"))
    )
    (net (code "28") (name "VMOD") (class "Default")
      (node (ref "J14") (pin "2") (pinfunction "2_2") (pintype "passive"))
      (node (ref "JMOD") (pin "1") (pinfunction "1_1") (pintype "passive"))
      (node (ref "JMODHT1") (pin "1") (pintype "passive"))
      (node (ref "RMOD") (pin "2") (pinfunction "2_2") (pintype "passive"))
      (node (ref "SW1") (pin "6") (pinfunction "N.C-2_6") (pintype "passive"))
      (node (ref "TP25") (pin "1") (pintype "passive"))
    )
    (net (code "29") (name "VMODH") (class "Default")
      (node (ref "JMODT1") (pin "1") (pintype "passive"))
      (node (ref "SW1") (pin "5") (pinfunction "COM-2_5") (pintype "passive"))
      (node (ref "TP5") (pin "1") (pintype "passive"))
    )
    (net (code "30") (name "VMODUSB") (class "Default")
      (node (ref "C46") (pin "1") (pinfunction "1_1") (pintype "passive"))
      (node (ref "C47") (pin "1") (pinfunction "1_1") (pintype "passive"))
      (node (ref "D10") (pin "5") (pinfunction "Vcc_5") (pintype "power_in"))
      (node (ref "J29") (pin "1") (pinfunction "VBUS_1") (pintype "power_in"))
      (node (ref "JBSB") (pin "2") (pinfunction "2_2") (pintype "passive"))
      (node (ref "R61") (pin "1") (pinfunction "1_1") (pintype "passive"))
      (node (ref "U19") (pin "1") (pinfunction "VDD_1") (pintype "power_in"))
      (node (ref "U19") (pin "3") (pinfunction "EN_3") (pintype "input"))
    )
    (net (code "31") (name "VSHLD") (class "Default")
      (node (ref "J18") (pin "2") (pinfunction "2_2") (pintype "passive"))
      (node (ref "JSHD") (pin "1") (pinfunction "1_1") (pintype "passive"))
      (node (ref "RSHD") (pin "2") (pinfunction "2_2") (pintype "passive"))
      (node (ref "TP19") (pin "1") (pintype "passive"))
    )
    (net (code "32") (name "VSYS") (class "Default")
      (node (ref "J14") (pin "3") (pinfunction "3_3") (pintype "passive"))
      (node (ref "J18") (pin "3") (pinfunction "3_3") (pintype "passive"))
      (node (ref "JMOD") (pin "2") (pinfunction "2_2") (pintype "passive"))
      (node (ref "JRMOD") (pin "2") (pinfunction "2_2") (pintype "passive"))
      (node (ref "JRSHD") (pin "2") (pinfunction "2_2") (pintype "passive"))
      (node (ref "JSHD") (pin "2") (pinfunction "2_2") (pintype "passive"))
      (node (ref "SW1") (pin "2") (pinfunction "COM-1_2") (pintype "passive"))
      (node (ref "TP15") (pin "1") (pintype "passive"))
    )
    (net (code "33") (name "unconnected-(D1-IO3-Pad4)") (class "Default")
      (node (ref "D1") (pin "4") (pinfunction "IO3_4") (pintype "passive+no_connect"))
    )
    (net (code "34") (name "unconnected-(D10-IO3-Pad4)") (class "Default")
      (node (ref "D10") (pin "4") (pinfunction "IO3_4") (pintype "passive+no_connect"))
    )
    (net (code "35") (name "unconnected-(J13-ID-Pad4)") (class "Default")
      (node (ref "J13") (pin "4") (pinfunction "ID_4") (pintype "passive+no_connect"))
    )
    (net (code "36") (name "unconnected-(J29-ID-Pad4)") (class "Default")
      (node (ref "J29") (pin "4") (pinfunction "ID_4") (pintype "passive+no_connect"))
    )
    (net (code "37") (name "unconnected-(SW1-N.O-1-Pad1)") (class "Default")
      (node (ref "SW1") (pin "1") (pinfunction "N.O-1_1") (pintype "passive"))
    )
    (net (code "38") (name "unconnected-(SW3-N.C-1-Pad3)") (class "Default")
      (node (ref "SW3") (pin "3") (pinfunction "N.C-1_3") (pintype "passive"))
    )
    (net (code "39") (name "unconnected-(SW3-N.C-2-Pad6)") (class "Default")
      (node (ref "SW3") (pin "6") (pinfunction "N.C-2_6") (pintype "passive"))
    )
    (net (code "40") (name "unconnected-(SW9-N.O.-3-Pad4)") (class "Default")
      (node (ref "SW9") (pin "4") (pinfunction "N.O.-3_4") (pintype "passive+no_connect"))
    )
    (net (code "41") (name "unconnected-(U1-NC-Pad4)") (class "Default")
      (node (ref "U1") (pin "4") (pinfunction "NC_4") (pintype "passive+no_connect"))
    )
    (net (code "42") (name "unconnected-(U2-NC-Pad4)") (class "Default")
      (node (ref "U2") (pin "4") (pinfunction "NC_4") (pintype "passive+no_connect"))
    )
    (net (code "43") (name "unconnected-(U8-NC-Pad4)") (class "Default")
      (node (ref "U8") (pin "4") (pinfunction "NC_4") (pintype "passive+no_connect"))
    )
    (net (code "44") (name "unconnected-(U10-NC-Pad4)") (class "Default")
      (node (ref "U10") (pin "4") (pinfunction "NC_4") (pintype "passive+no_connect"))
    )
    (net (code "45") (name "unconnected-(U13-NC-Pad4)") (class "Default")
      (node (ref "U13") (pin "4") (pinfunction "NC_4") (pintype "passive+no_connect"))
    )
    (net (code "46") (name "unconnected-(U16-NC{slash}ADJ-Pad4)") (class "Default")
      (node (ref "U16") (pin "4") (pinfunction "NC/ADJ_4") (pintype "passive+no_connect"))
    )
    (net (code "47") (name "unconnected-(U18-NC-Pad4)") (class "Default")
      (node (ref "U18") (pin "4") (pinfunction "NC_4") (pintype "passive+no_connect"))
    )
    (net (code "48") (name "unconnected-(U19-NC-Pad4)") (class "Default")
      (node (ref "U19") (pin "4") (pinfunction "NC_4") (pintype "passive+no_connect"))
    )
  )
)
